# BlankSlate.net
KiCad netlist of a schematic drawn in EAGLE
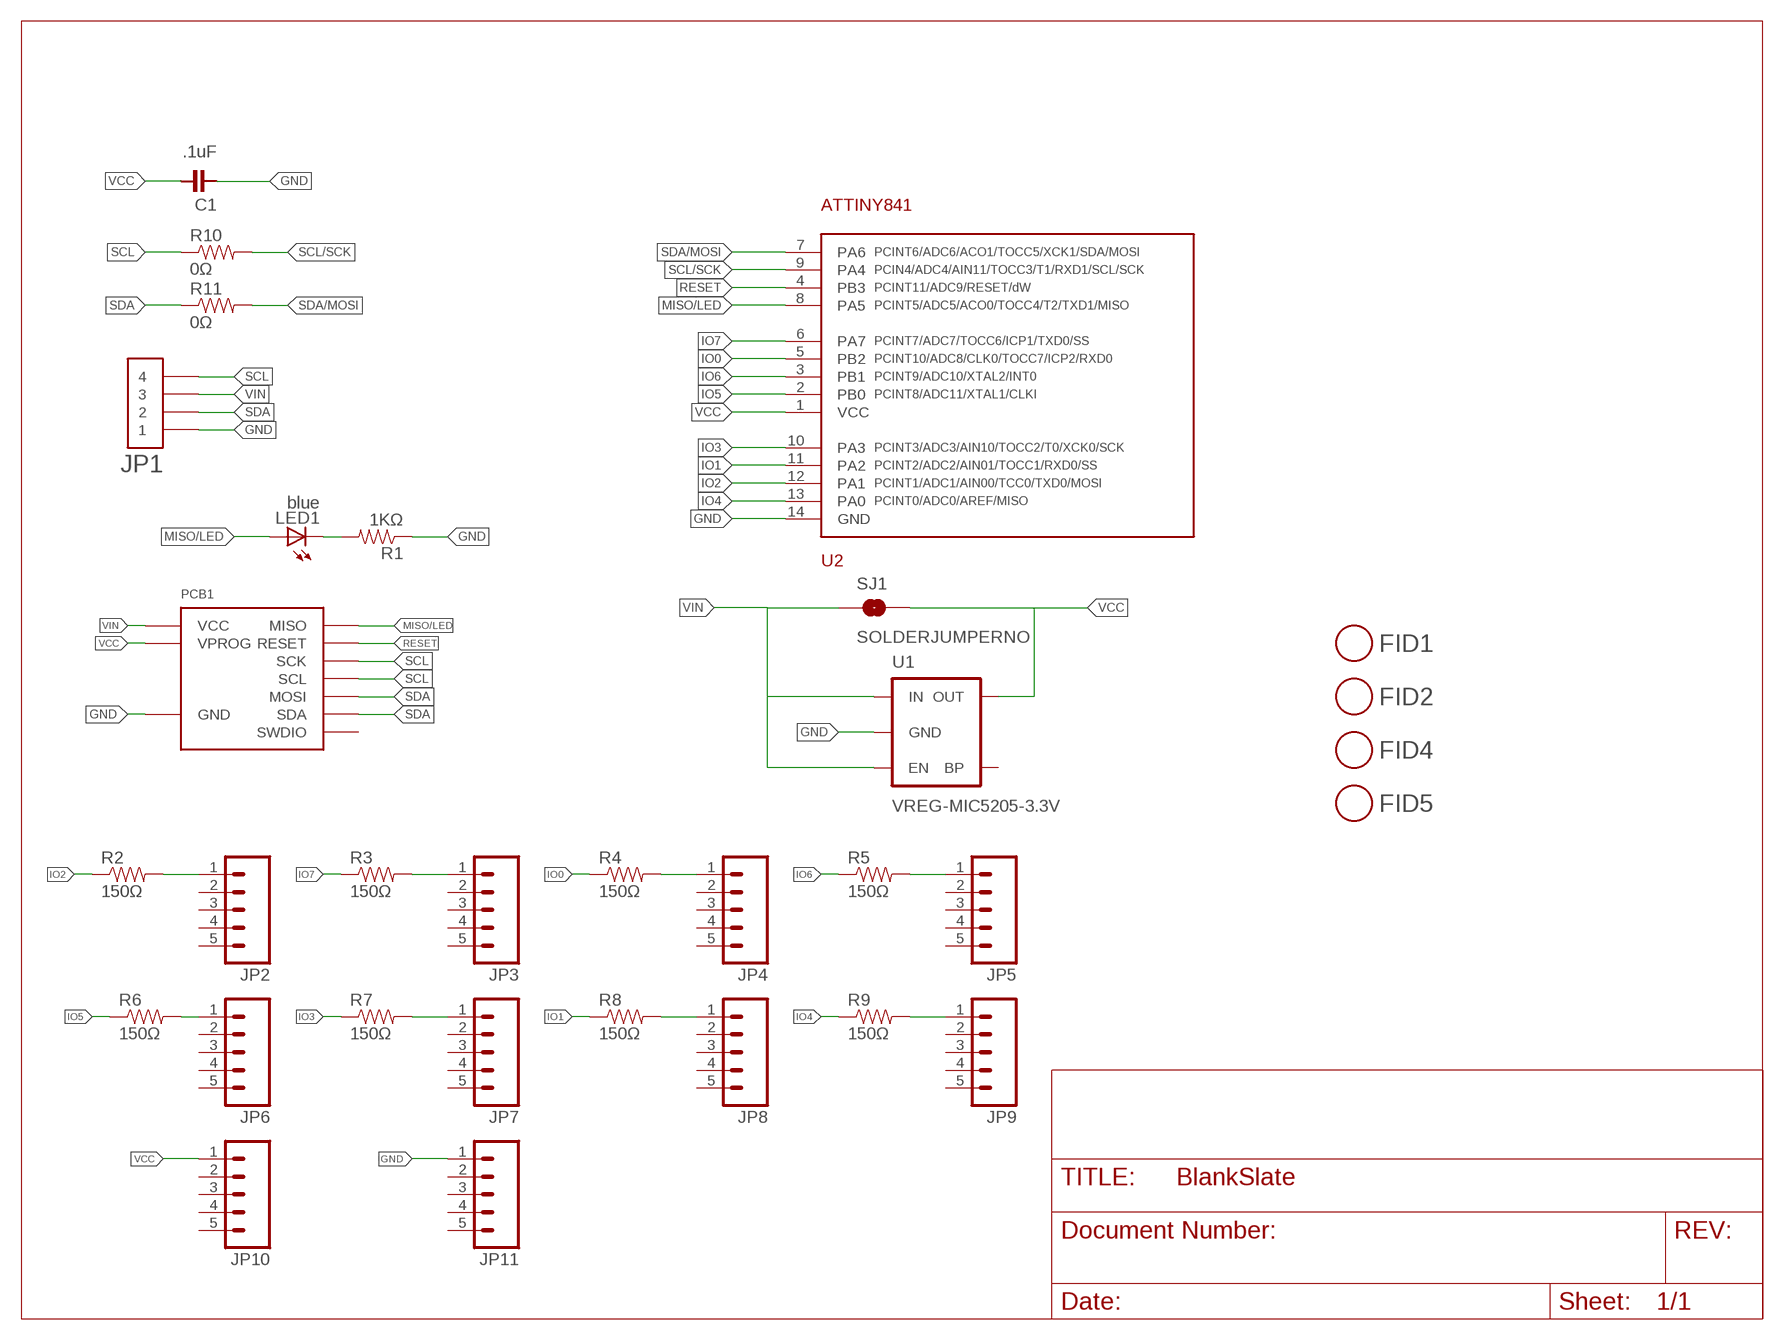
[diagram p0: schematic, sheet 1]

(export (version "E")
  (design (tool "Eeschema 10.0.6"))
  (components
    (comp (ref "C1")
      (value ".1uF")
      (footprint "eagle-import:0603")
      (fields (field (name "PARTNUM") "C0603C104K5RACTU"))
      (libsource (lib "eagle-import") (part "CAPACITOR-.1UF"))
    )
    (comp (ref "FID1")
      (value "FIDUCIAL")
      (footprint "eagle-import:FIDUCIAL_1MM")
      (fields (field (name "BOM") "EXCLUDE"))
      (libsource (lib "eagle-import") (part "FIDUCIAL"))
    )
    (comp (ref "FID2")
      (value "FIDUCIAL")
      (footprint "eagle-import:FIDUCIAL_1MM")
      (fields (field (name "BOM") "EXCLUDE"))
      (libsource (lib "eagle-import") (part "FIDUCIAL"))
    )
    (comp (ref "FID4")
      (value "FIDUCIAL")
      (footprint "eagle-import:FIDUCIAL_1MM")
      (fields (field (name "BOM") "EXCLUDE"))
      (libsource (lib "eagle-import") (part "FIDUCIAL"))
    )
    (comp (ref "FID5")
      (value "FIDUCIAL")
      (footprint "eagle-import:FIDUCIAL_1MM")
      (fields (field (name "BOM") "EXCLUDE"))
      (libsource (lib "eagle-import") (part "FIDUCIAL"))
    )
    (comp (ref "JP1")
      (value "HEADER-1X4-AMPMODU")
      (footprint "eagle-import:AMPMODU-4P")
      (fields (field (name "PARTNUM") "147721-3"))
      (libsource (lib "eagle-import") (part "HEADER-1X4-AMPMODU"))
    )
    (comp (ref "JP2")
      (value "M05NO_SILK")
      (footprint "eagle-import:1X05_NO_SILK")
      (fields (field (name "PARTNUM") "EXCLUDE"))
      (libsource (lib "eagle-import") (part "M05NO_SILK"))
    )
    (comp (ref "JP3")
      (value "M05NO_SILK")
      (footprint "eagle-import:1X05_NO_SILK")
      (fields (field (name "PARTNUM") "EXCLUDE"))
      (libsource (lib "eagle-import") (part "M05NO_SILK"))
    )
    (comp (ref "JP4")
      (value "M05NO_SILK")
      (footprint "eagle-import:1X05_NO_SILK")
      (fields (field (name "PARTNUM") "EXCLUDE"))
      (libsource (lib "eagle-import") (part "M05NO_SILK"))
    )
    (comp (ref "JP5")
      (value "M05NO_SILK")
      (footprint "eagle-import:1X05_NO_SILK")
      (fields (field (name "PARTNUM") "EXCLUDE"))
      (libsource (lib "eagle-import") (part "M05NO_SILK"))
    )
    (comp (ref "JP6")
      (value "M05NO_SILK")
      (footprint "eagle-import:1X05_NO_SILK")
      (fields (field (name "PARTNUM") "EXCLUDE"))
      (libsource (lib "eagle-import") (part "M05NO_SILK"))
    )
    (comp (ref "JP7")
      (value "M05NO_SILK")
      (footprint "eagle-import:1X05_NO_SILK")
      (fields (field (name "PARTNUM") "EXCLUDE"))
      (libsource (lib "eagle-import") (part "M05NO_SILK"))
    )
    (comp (ref "JP8")
      (value "M05NO_SILK")
      (footprint "eagle-import:1X05_NO_SILK")
      (fields (field (name "PARTNUM") "EXCLUDE"))
      (libsource (lib "eagle-import") (part "M05NO_SILK"))
    )
    (comp (ref "JP9")
      (value "M05NO_SILK")
      (footprint "eagle-import:1X05_NO_SILK")
      (fields (field (name "PARTNUM") "EXCLUDE"))
      (libsource (lib "eagle-import") (part "M05NO_SILK"))
    )
    (comp (ref "JP10")
      (value "M05NO_SILK")
      (footprint "eagle-import:1X05_NO_SILK")
      (fields (field (name "PARTNUM") "EXCLUDE"))
      (libsource (lib "eagle-import") (part "M05NO_SILK"))
    )
    (comp (ref "JP11")
      (value "M05NO_SILK")
      (footprint "eagle-import:1X05_NO_SILK")
      (fields (field (name "PARTNUM") "EXCLUDE"))
      (libsource (lib "eagle-import") (part "M05NO_SILK"))
    )
    (comp (ref "LED1")
      (value "blue")
      (footprint "eagle-import:0805-LED")
      (fields (field (name "PARTNUM") "LTST-C171TBKT"))
      (libsource (lib "eagle-import") (part "LED-0805-BLUE"))
    )
    (comp (ref "PCB1")
      (value "DEVICE-PCB")
      (footprint "eagle-import:DEVICE-PCB")
      (fields (field (name "PARTNUM") "Blank Slate PCB"))
      (libsource (lib "eagle-import") (part "DEVICE-PCB"))
    )
    (comp (ref "R1")
      (value "1KΩ")
      (footprint "eagle-import:0603")
      (fields (field (name "PARTNUM") "ERJ-3EKF1001V"))
      (libsource (lib "eagle-import") (part "RESISTOR-1KΩ"))
    )
    (comp (ref "R2")
      (value "150Ω")
      (footprint "eagle-import:0603")
      (fields (field (name "PARTNUM") "ERJ-3EKF1500V"))
      (libsource (lib "eagle-import") (part "RESISTOR-150Ω"))
    )
    (comp (ref "R3")
      (value "150Ω")
      (footprint "eagle-import:0603")
      (fields (field (name "PARTNUM") "ERJ-3EKF1500V"))
      (libsource (lib "eagle-import") (part "RESISTOR-150Ω"))
    )
    (comp (ref "R4")
      (value "150Ω")
      (footprint "eagle-import:0603")
      (fields (field (name "PARTNUM") "ERJ-3EKF1500V"))
      (libsource (lib "eagle-import") (part "RESISTOR-150Ω"))
    )
    (comp (ref "R5")
      (value "150Ω")
      (footprint "eagle-import:0603")
      (fields (field (name "PARTNUM") "ERJ-3EKF1500V"))
      (libsource (lib "eagle-import") (part "RESISTOR-150Ω"))
    )
    (comp (ref "R6")
      (value "150Ω")
      (footprint "eagle-import:0603")
      (fields (field (name "PARTNUM") "ERJ-3EKF1500V"))
      (libsource (lib "eagle-import") (part "RESISTOR-150Ω"))
    )
    (comp (ref "R7")
      (value "150Ω")
      (footprint "eagle-import:0603")
      (fields (field (name "PARTNUM") "ERJ-3EKF1500V"))
      (libsource (lib "eagle-import") (part "RESISTOR-150Ω"))
    )
    (comp (ref "R8")
      (value "150Ω")
      (footprint "eagle-import:0603")
      (fields (field (name "PARTNUM") "ERJ-3EKF1500V"))
      (libsource (lib "eagle-import") (part "RESISTOR-150Ω"))
    )
    (comp (ref "R9")
      (value "150Ω")
      (footprint "eagle-import:0603")
      (fields (field (name "PARTNUM") "ERJ-3EKF1500V"))
      (libsource (lib "eagle-import") (part "RESISTOR-150Ω"))
    )
    (comp (ref "R10")
      (value "0Ω")
      (footprint "eagle-import:0603")
      (fields (field (name "PARTNUM") "ERJ-3GEY0R00V"))
      (libsource (lib "eagle-import") (part "RESISTOR-0Ω"))
    )
    (comp (ref "R11")
      (value "0Ω")
      (footprint "eagle-import:0603")
      (fields (field (name "PARTNUM") "ERJ-3GEY0R00V"))
      (libsource (lib "eagle-import") (part "RESISTOR-0Ω"))
    )
    (comp (ref "SJ1")
      (value "SOLDERJUMPERNO")
      (footprint "eagle-import:SJ_2S-NO")
      (libsource (lib "eagle-import") (part "SOLDERJUMPERNO"))
    )
    (comp (ref "U1")
      (value "VREG-MIC5205-3.3V")
      (footprint "eagle-import:SOT23-5")
      (fields (field (name "PARTNUM") "MIC5205-3.3YM5 TR"))
      (libsource (lib "eagle-import") (part "VREG-MIC5205-3.3V"))
    )
    (comp (ref "U2")
      (value "ATTINY841")
      (footprint "eagle-import:SOIC-14")
      (fields (field (name "PARTNUM") "ATTINY841-SSUR"))
      (libsource (lib "eagle-import") (part "ATTINY841"))
    )
  )
  (nets
    (net (code "1") (name "GND") (class "Default")
      (node (ref "C1") (pin "2") (pinfunction "2_2") (pintype "passive"))
      (node (ref "JP1") (pin "P$1") (pinfunction "1_P$1") (pintype "bidirectional"))
      (node (ref "JP1") (pin "P$2") (pinfunction "1_P$2") (pintype "bidirectional"))
      (node (ref "JP11") (pin "1") (pinfunction "1_1") (pintype "passive"))
      (node (ref "PCB1") (pin "GND") (pinfunction "GND_GND") (pintype "bidirectional"))
      (node (ref "R1") (pin "1") (pinfunction "1_1") (pintype "passive"))
      (node (ref "U1") (pin "2") (pinfunction "GND_2") (pintype "input"))
      (node (ref "U2") (pin "14") (pinfunction "GND_14") (pintype "bidirectional"))
    )
    (net (code "2") (name "IO0") (class "Default")
      (node (ref "R4") (pin "1") (pinfunction "1_1") (pintype "passive"))
      (node (ref "U2") (pin "5") (pinfunction "PB2_5") (pintype "bidirectional"))
    )
    (net (code "3") (name "IO1") (class "Default")
      (node (ref "R8") (pin "1") (pinfunction "1_1") (pintype "passive"))
      (node (ref "U2") (pin "11") (pinfunction "PA2_11") (pintype "bidirectional"))
    )
    (net (code "4") (name "IO2") (class "Default")
      (node (ref "R2") (pin "1") (pinfunction "1_1") (pintype "passive"))
      (node (ref "U2") (pin "12") (pinfunction "PA1_12") (pintype "bidirectional"))
    )
    (net (code "5") (name "IO3") (class "Default")
      (node (ref "R7") (pin "1") (pinfunction "1_1") (pintype "passive"))
      (node (ref "U2") (pin "10") (pinfunction "PA3_10") (pintype "bidirectional"))
    )
    (net (code "6") (name "IO4") (class "Default")
      (node (ref "R9") (pin "1") (pinfunction "1_1") (pintype "passive"))
      (node (ref "U2") (pin "13") (pinfunction "PA0_13") (pintype "bidirectional"))
    )
    (net (code "7") (name "IO5") (class "Default")
      (node (ref "R6") (pin "1") (pinfunction "1_1") (pintype "passive"))
      (node (ref "U2") (pin "2") (pinfunction "PB0_2") (pintype "bidirectional"))
    )
    (net (code "8") (name "IO6") (class "Default")
      (node (ref "R5") (pin "1") (pinfunction "1_1") (pintype "passive"))
      (node (ref "U2") (pin "3") (pinfunction "PB1_3") (pintype "bidirectional"))
    )
    (net (code "9") (name "IO7") (class "Default")
      (node (ref "R3") (pin "1") (pinfunction "1_1") (pintype "passive"))
      (node (ref "U2") (pin "6") (pinfunction "PA7_6") (pintype "bidirectional"))
    )
    (net (code "10") (name "MISO{slash}LED") (class "Default")
      (node (ref "LED1") (pin "A") (pinfunction "A_A") (pintype "passive"))
      (node (ref "PCB1") (pin "MISO") (pinfunction "MISO_MISO") (pintype "bidirectional"))
      (node (ref "U2") (pin "8") (pinfunction "PA5_8") (pintype "bidirectional"))
    )
    (net (code "11") (name "Net-(JP2-Pad1)") (class "Default")
      (node (ref "JP2") (pin "1") (pinfunction "1_1") (pintype "passive"))
      (node (ref "R2") (pin "2") (pinfunction "2_2") (pintype "passive"))
    )
    (net (code "12") (name "Net-(JP3-Pad1)") (class "Default")
      (node (ref "JP3") (pin "1") (pinfunction "1_1") (pintype "passive"))
      (node (ref "R3") (pin "2") (pinfunction "2_2") (pintype "passive"))
    )
    (net (code "13") (name "Net-(JP4-Pad1)") (class "Default")
      (node (ref "JP4") (pin "1") (pinfunction "1_1") (pintype "passive"))
      (node (ref "R4") (pin "2") (pinfunction "2_2") (pintype "passive"))
    )
    (net (code "14") (name "Net-(JP5-Pad1)") (class "Default")
      (node (ref "JP5") (pin "1") (pinfunction "1_1") (pintype "passive"))
      (node (ref "R5") (pin "2") (pinfunction "2_2") (pintype "passive"))
    )
    (net (code "15") (name "Net-(JP6-Pad1)") (class "Default")
      (node (ref "JP6") (pin "1") (pinfunction "1_1") (pintype "passive"))
      (node (ref "R6") (pin "2") (pinfunction "2_2") (pintype "passive"))
    )
    (net (code "16") (name "Net-(JP7-Pad1)") (class "Default")
      (node (ref "JP7") (pin "1") (pinfunction "1_1") (pintype "passive"))
      (node (ref "R7") (pin "2") (pinfunction "2_2") (pintype "passive"))
    )
    (net (code "17") (name "Net-(JP8-Pad1)") (class "Default")
      (node (ref "JP8") (pin "1") (pinfunction "1_1") (pintype "passive"))
      (node (ref "R8") (pin "2") (pinfunction "2_2") (pintype "passive"))
    )
    (net (code "18") (name "Net-(JP9-Pad1)") (class "Default")
      (node (ref "JP9") (pin "1") (pinfunction "1_1") (pintype "passive"))
      (node (ref "R9") (pin "2") (pinfunction "2_2") (pintype "passive"))
    )
    (net (code "19") (name "Net-(LED1-PadC)") (class "Default")
      (node (ref "LED1") (pin "C") (pinfunction "C_C") (pintype "passive"))
      (node (ref "R1") (pin "2") (pinfunction "2_2") (pintype "passive"))
    )
    (net (code "20") (name "RESET") (class "Default")
      (node (ref "PCB1") (pin "RESET") (pinfunction "RESET_RESET") (pintype "bidirectional"))
      (node (ref "U2") (pin "4") (pinfunction "PB3_4") (pintype "bidirectional"))
    )
    (net (code "21") (name "SCL") (class "Default")
      (node (ref "JP1") (pin "P$7") (pinfunction "4_P$7") (pintype "bidirectional"))
      (node (ref "JP1") (pin "P$8") (pinfunction "4_P$8") (pintype "bidirectional"))
      (node (ref "PCB1") (pin "CLK") (pinfunction "SCK_CLK") (pintype "bidirectional"))
      (node (ref "PCB1") (pin "SCL") (pinfunction "SCL_SCL") (pintype "bidirectional"))
      (node (ref "R10") (pin "1") (pinfunction "1_1") (pintype "passive"))
    )
    (net (code "22") (name "SCL{slash}SCK") (class "Default")
      (node (ref "R10") (pin "2") (pinfunction "2_2") (pintype "passive"))
      (node (ref "U2") (pin "9") (pinfunction "PA4_9") (pintype "bidirectional"))
    )
    (net (code "23") (name "SDA") (class "Default")
      (node (ref "JP1") (pin "P$3") (pinfunction "2_P$3") (pintype "bidirectional"))
      (node (ref "JP1") (pin "P$4") (pinfunction "2_P$4") (pintype "bidirectional"))
      (node (ref "PCB1") (pin "MOSI") (pinfunction "MOSI_MOSI") (pintype "bidirectional"))
      (node (ref "PCB1") (pin "SDA") (pinfunction "SDA_SDA") (pintype "bidirectional"))
      (node (ref "R11") (pin "1") (pinfunction "1_1") (pintype "passive"))
    )
    (net (code "24") (name "SDA{slash}MOSI") (class "Default")
      (node (ref "R11") (pin "2") (pinfunction "2_2") (pintype "passive"))
      (node (ref "U2") (pin "7") (pinfunction "PA6_7") (pintype "bidirectional"))
    )
    (net (code "25") (name "VCC") (class "Default")
      (node (ref "C1") (pin "1") (pinfunction "1_1") (pintype "passive"))
      (node (ref "JP10") (pin "1") (pinfunction "1_1") (pintype "passive"))
      (node (ref "PCB1") (pin "VPROG") (pinfunction "VPROG_VPROG") (pintype "bidirectional"))
      (node (ref "SJ1") (pin "2") (pinfunction "2_2") (pintype "passive"))
      (node (ref "U1") (pin "5") (pinfunction "OUT_5") (pintype "passive"))
      (node (ref "U2") (pin "1") (pinfunction "VCC_1") (pintype "bidirectional"))
    )
    (net (code "26") (name "VIN") (class "Default")
      (node (ref "JP1") (pin "P$5") (pinfunction "3_P$5") (pintype "bidirectional"))
      (node (ref "JP1") (pin "P$6") (pinfunction "3_P$6") (pintype "bidirectional"))
      (node (ref "PCB1") (pin "VCC") (pinfunction "VCC_VCC") (pintype "bidirectional"))
      (node (ref "SJ1") (pin "1") (pinfunction "1_1") (pintype "passive"))
      (node (ref "U1") (pin "1") (pinfunction "IN_1") (pintype "input"))
      (node (ref "U1") (pin "3") (pinfunction "EN_3") (pintype "input"))
    )
    (net (code "27") (name "unconnected-(JP2-Pad2)") (class "Default")
      (node (ref "JP2") (pin "2") (pinfunction "2_2") (pintype "passive"))
    )
    (net (code "28") (name "unconnected-(JP2-Pad3)") (class "Default")
      (node (ref "JP2") (pin "3") (pinfunction "3_3") (pintype "passive"))
    )
    (net (code "29") (name "unconnected-(JP2-Pad4)") (class "Default")
      (node (ref "JP2") (pin "4") (pinfunction "4_4") (pintype "passive"))
    )
    (net (code "30") (name "unconnected-(JP2-Pad5)") (class "Default")
      (node (ref "JP2") (pin "5") (pinfunction "5_5") (pintype "passive"))
    )
    (net (code "31") (name "unconnected-(JP3-Pad2)") (class "Default")
      (node (ref "JP3") (pin "2") (pinfunction "2_2") (pintype "passive"))
    )
    (net (code "32") (name "unconnected-(JP3-Pad3)") (class "Default")
      (node (ref "JP3") (pin "3") (pinfunction "3_3") (pintype "passive"))
    )
    (net (code "33") (name "unconnected-(JP3-Pad4)") (class "Default")
      (node (ref "JP3") (pin "4") (pinfunction "4_4") (pintype "passive"))
    )
    (net (code "34") (name "unconnected-(JP3-Pad5)") (class "Default")
      (node (ref "JP3") (pin "5") (pinfunction "5_5") (pintype "passive"))
    )
    (net (code "35") (name "unconnected-(JP4-Pad2)") (class "Default")
      (node (ref "JP4") (pin "2") (pinfunction "2_2") (pintype "passive"))
    )
    (net (code "36") (name "unconnected-(JP4-Pad3)") (class "Default")
      (node (ref "JP4") (pin "3") (pinfunction "3_3") (pintype "passive"))
    )
    (net (code "37") (name "unconnected-(JP4-Pad4)") (class "Default")
      (node (ref "JP4") (pin "4") (pinfunction "4_4") (pintype "passive"))
    )
    (net (code "38") (name "unconnected-(JP4-Pad5)") (class "Default")
      (node (ref "JP4") (pin "5") (pinfunction "5_5") (pintype "passive"))
    )
    (net (code "39") (name "unconnected-(JP5-Pad2)") (class "Default")
      (node (ref "JP5") (pin "2") (pinfunction "2_2") (pintype "passive"))
    )
    (net (code "40") (name "unconnected-(JP5-Pad3)") (class "Default")
      (node (ref "JP5") (pin "3") (pinfunction "3_3") (pintype "passive"))
    )
    (net (code "41") (name "unconnected-(JP5-Pad4)") (class "Default")
      (node (ref "JP5") (pin "4") (pinfunction "4_4") (pintype "passive"))
    )
    (net (code "42") (name "unconnected-(JP5-Pad5)") (class "Default")
      (node (ref "JP5") (pin "5") (pinfunction "5_5") (pintype "passive"))
    )
    (net (code "43") (name "unconnected-(JP6-Pad2)") (class "Default")
      (node (ref "JP6") (pin "2") (pinfunction "2_2") (pintype "passive"))
    )
    (net (code "44") (name "unconnected-(JP6-Pad3)") (class "Default")
      (node (ref "JP6") (pin "3") (pinfunction "3_3") (pintype "passive"))
    )
    (net (code "45") (name "unconnected-(JP6-Pad4)") (class "Default")
      (node (ref "JP6") (pin "4") (pinfunction "4_4") (pintype "passive"))
    )
    (net (code "46") (name "unconnected-(JP6-Pad5)") (class "Default")
      (node (ref "JP6") (pin "5") (pinfunction "5_5") (pintype "passive"))
    )
    (net (code "47") (name "unconnected-(JP7-Pad2)") (class "Default")
      (node (ref "JP7") (pin "2") (pinfunction "2_2") (pintype "passive"))
    )
    (net (code "48") (name "unconnected-(JP7-Pad3)") (class "Default")
      (node (ref "JP7") (pin "3") (pinfunction "3_3") (pintype "passive"))
    )
    (net (code "49") (name "unconnected-(JP7-Pad4)") (class "Default")
      (node (ref "JP7") (pin "4") (pinfunction "4_4") (pintype "passive"))
    )
    (net (code "50") (name "unconnected-(JP7-Pad5)") (class "Default")
      (node (ref "JP7") (pin "5") (pinfunction "5_5") (pintype "passive"))
    )
    (net (code "51") (name "unconnected-(JP8-Pad2)") (class "Default")
      (node (ref "JP8") (pin "2") (pinfunction "2_2") (pintype "passive"))
    )
    (net (code "52") (name "unconnected-(JP8-Pad3)") (class "Default")
      (node (ref "JP8") (pin "3") (pinfunction "3_3") (pintype "passive"))
    )
    (net (code "53") (name "unconnected-(JP8-Pad4)") (class "Default")
      (node (ref "JP8") (pin "4") (pinfunction "4_4") (pintype "passive"))
    )
    (net (code "54") (name "unconnected-(JP8-Pad5)") (class "Default")
      (node (ref "JP8") (pin "5") (pinfunction "5_5") (pintype "passive"))
    )
    (net (code "55") (name "unconnected-(JP9-Pad2)") (class "Default")
      (node (ref "JP9") (pin "2") (pinfunction "2_2") (pintype "passive"))
    )
    (net (code "56") (name "unconnected-(JP9-Pad3)") (class "Default")
      (node (ref "JP9") (pin "3") (pinfunction "3_3") (pintype "passive"))
    )
    (net (code "57") (name "unconnected-(JP9-Pad4)") (class "Default")
      (node (ref "JP9") (pin "4") (pinfunction "4_4") (pintype "passive"))
    )
    (net (code "58") (name "unconnected-(JP9-Pad5)") (class "Default")
      (node (ref "JP9") (pin "5") (pinfunction "5_5") (pintype "passive"))
    )
    (net (code "59") (name "unconnected-(JP10-Pad2)") (class "Default")
      (node (ref "JP10") (pin "2") (pinfunction "2_2") (pintype "passive"))
    )
    (net (code "60") (name "unconnected-(JP10-Pad3)") (class "Default")
      (node (ref "JP10") (pin "3") (pinfunction "3_3") (pintype "passive"))
    )
    (net (code "61") (name "unconnected-(JP10-Pad4)") (class "Default")
      (node (ref "JP10") (pin "4") (pinfunction "4_4") (pintype "passive"))
    )
    (net (code "62") (name "unconnected-(JP10-Pad5)") (class "Default")
      (node (ref "JP10") (pin "5") (pinfunction "5_5") (pintype "passive"))
    )
    (net (code "63") (name "unconnected-(JP11-Pad2)") (class "Default")
      (node (ref "JP11") (pin "2") (pinfunction "2_2") (pintype "passive"))
    )
    (net (code "64") (name "unconnected-(JP11-Pad3)") (class "Default")
      (node (ref "JP11") (pin "3") (pinfunction "3_3") (pintype "passive"))
    )
    (net (code "65") (name "unconnected-(JP11-Pad4)") (class "Default")
      (node (ref "JP11") (pin "4") (pinfunction "4_4") (pintype "passive"))
    )
    (net (code "66") (name "unconnected-(JP11-Pad5)") (class "Default")
      (node (ref "JP11") (pin "5") (pinfunction "5_5") (pintype "passive"))
    )
    (net (code "67") (name "unconnected-(PCB1-PadSWDIO)") (class "Default")
      (node (ref "PCB1") (pin "SWDIO") (pinfunction "SWDIO_SWDIO") (pintype "bidirectional"))
    )
    (net (code "68") (name "unconnected-(U1-BP-Pad4)") (class "Default")
      (node (ref "U1") (pin "4") (pinfunction "BP_4") (pintype "input"))
    )
  )
)
